# OSSC_HDMI_Audio_v1_5_A4a.net
KiCad netlist of a schematic drawn in EAGLE
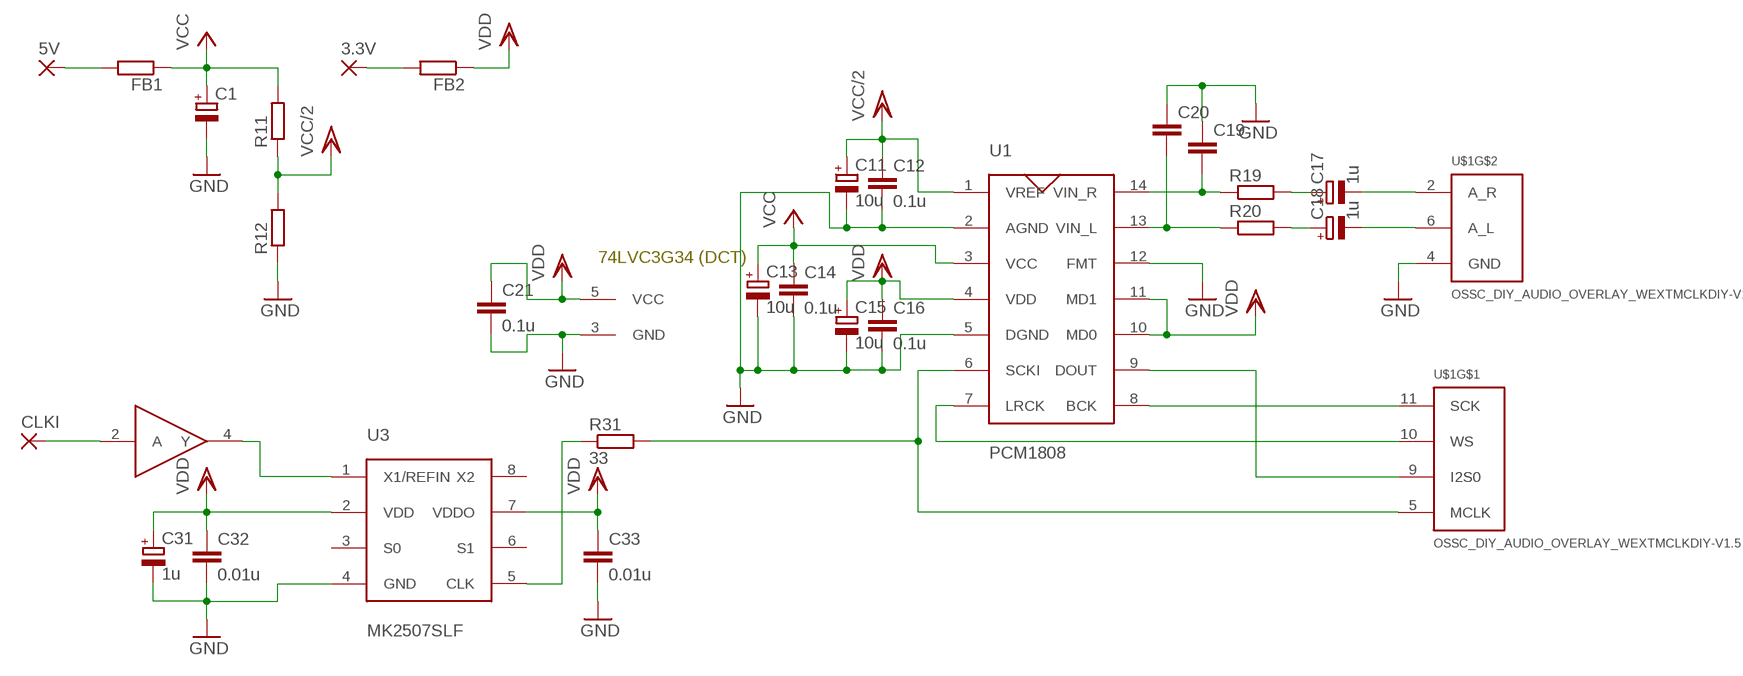
[diagram p0: schematic, sheet 1]

(export (version "E")
  (design (tool "Eeschema 10.0.6"))
  (components
    (comp (ref "3.3V")
      (value "SMD2")
      (footprint "eagle-import:SMD1,27-2,54")
      (libsource (lib "eagle-import") (part "SMD2"))
    )
    (comp (ref "5V")
      (value "SMD2")
      (footprint "eagle-import:SMD1,27-2,54")
      (libsource (lib "eagle-import") (part "SMD2"))
    )
    (comp (ref "C1")
      (value "CPOL-EUSMCC")
      (footprint "eagle-import:SMC_C")
      (libsource (lib "eagle-import") (part "CPOL-EUSMCC"))
    )
    (comp (ref "C11")
      (value "10u")
      (footprint "eagle-import:SMC_A")
      (libsource (lib "eagle-import") (part "CPOL-EUSMCA"))
    )
    (comp (ref "C12")
      (value "0.1u")
      (footprint "eagle-import:C0603")
      (libsource (lib "eagle-import") (part "C-EUC0603"))
    )
    (comp (ref "C13")
      (value "10u")
      (footprint "eagle-import:SMC_A")
      (libsource (lib "eagle-import") (part "CPOL-EUSMCA"))
    )
    (comp (ref "C14")
      (value "0.1u")
      (footprint "eagle-import:C0603")
      (libsource (lib "eagle-import") (part "C-EUC0603"))
    )
    (comp (ref "C15")
      (value "10u")
      (footprint "eagle-import:SMC_A")
      (libsource (lib "eagle-import") (part "CPOL-EUSMCA"))
    )
    (comp (ref "C16")
      (value "0.1u")
      (footprint "eagle-import:C0603")
      (libsource (lib "eagle-import") (part "C-EUC0603"))
    )
    (comp (ref "C17")
      (value "1u")
      (footprint "eagle-import:SMC_A")
      (libsource (lib "eagle-import") (part "CPOL-EUSMCA"))
    )
    (comp (ref "C18")
      (value "1u")
      (footprint "eagle-import:SMC_A")
      (libsource (lib "eagle-import") (part "CPOL-EUSMCA"))
    )
    (comp (ref "C19")
      (value "C-EUC0603")
      (footprint "eagle-import:C0603")
      (libsource (lib "eagle-import") (part "C-EUC0603"))
    )
    (comp (ref "C20")
      (value "C-EUC0603")
      (footprint "eagle-import:C0603")
      (libsource (lib "eagle-import") (part "C-EUC0603"))
    )
    (comp (ref "C21")
      (value "0.1u")
      (footprint "eagle-import:C0603")
      (libsource (lib "eagle-import") (part "C-EUC0603"))
    )
    (comp (ref "C31")
      (value "1u")
      (footprint "eagle-import:SMC_A")
      (libsource (lib "eagle-import") (part "CPOL-EUSMCA"))
    )
    (comp (ref "C32")
      (value "0.01u")
      (footprint "eagle-import:C0603")
      (libsource (lib "eagle-import") (part "C-EUC0603"))
    )
    (comp (ref "C33")
      (value "0.01u")
      (footprint "eagle-import:C0603")
      (libsource (lib "eagle-import") (part "C-EUC0603"))
    )
    (comp (ref "CLKI")
      (value "SMD2")
      (footprint "eagle-import:SMD1,27-2,54")
      (libsource (lib "eagle-import") (part "SMD2"))
    )
    (comp (ref "FB1")
      (value "R-EU_R0603")
      (footprint "eagle-import:R0603")
      (libsource (lib "eagle-import") (part "R-EU_R0603"))
    )
    (comp (ref "FB2")
      (value "R-EU_R0603")
      (footprint "eagle-import:R0603")
      (libsource (lib "eagle-import") (part "R-EU_R0603"))
    )
    (comp (ref "R11")
      (value "R-EU_R0603")
      (footprint "eagle-import:R0603")
      (libsource (lib "eagle-import") (part "R-EU_R0603"))
    )
    (comp (ref "R12")
      (value "R-EU_R0603")
      (footprint "eagle-import:R0603")
      (libsource (lib "eagle-import") (part "R-EU_R0603"))
    )
    (comp (ref "R19")
      (value "R-EU_R0603")
      (footprint "eagle-import:R0603")
      (libsource (lib "eagle-import") (part "R-EU_R0603"))
    )
    (comp (ref "R20")
      (value "R-EU_R0603")
      (footprint "eagle-import:R0603")
      (libsource (lib "eagle-import") (part "R-EU_R0603"))
    )
    (comp (ref "R31")
      (value "33")
      (footprint "eagle-import:R0603")
      (libsource (lib "eagle-import") (part "R-EU_R0603"))
    )
    (comp (ref "U$1")
      (value "OSSC_DIY_AUDIO_OVERLAY_WEXTMCLKDIY-V1.5")
      (footprint "eagle-import:OSSC_OVERLAY_V1.5_WEXTMCLK")
      (libsource (lib "eagle-import") (part "OSSC_DIY_AUDIO_OVERLAY_WEXTMCLKDIY-V1.5"))
    )
    (comp (ref "U1")
      (value "PCM1808")
      (footprint "eagle-import:PCM1808")
      (libsource (lib "eagle-import") (part "PCM1808"))
    )
    (comp (ref "U2")
      (value "74LVC1G34")
      (footprint "eagle-import:74LVC1G34DCK")
      (libsource (lib "eagle-import") (part "74LVC1G34"))
    )
    (comp (ref "U3")
      (value "MK2507SLF")
      (footprint "eagle-import:SOIC8")
      (libsource (lib "eagle-import") (part "MK2507SLF"))
    )
  )
  (nets
    (net (code "1") (name "GND") (class "Default")
      (node (ref "C1") (pin "-") (pinfunction "-_-") (pintype "passive"))
      (node (ref "C11") (pin "-") (pinfunction "-_-") (pintype "passive"))
      (node (ref "C12") (pin "2") (pinfunction "2_2") (pintype "passive"))
      (node (ref "C13") (pin "-") (pinfunction "-_-") (pintype "passive"))
      (node (ref "C14") (pin "2") (pinfunction "2_2") (pintype "passive"))
      (node (ref "C15") (pin "-") (pinfunction "-_-") (pintype "passive"))
      (node (ref "C16") (pin "2") (pinfunction "2_2") (pintype "passive"))
      (node (ref "C19") (pin "1") (pinfunction "1_1") (pintype "passive"))
      (node (ref "C20") (pin "1") (pinfunction "1_1") (pintype "passive"))
      (node (ref "C21") (pin "2") (pinfunction "2_2") (pintype "passive"))
      (node (ref "C31") (pin "-") (pinfunction "-_-") (pintype "passive"))
      (node (ref "C32") (pin "2") (pinfunction "2_2") (pintype "passive"))
      (node (ref "C33") (pin "2") (pinfunction "2_2") (pintype "passive"))
      (node (ref "R12") (pin "1") (pinfunction "1_1") (pintype "passive"))
      (node (ref "U$1") (pin "4") (pinfunction "GND_4") (pintype "bidirectional"))
      (node (ref "U1") (pin "12") (pinfunction "FMT_12") (pintype "bidirectional"))
      (node (ref "U1") (pin "2") (pinfunction "AGND_2") (pintype "bidirectional"))
      (node (ref "U1") (pin "5") (pinfunction "DGND_5") (pintype "bidirectional"))
      (node (ref "U2") (pin "3") (pinfunction "GND_3") (pintype "bidirectional"))
      (node (ref "U3") (pin "4") (pinfunction "GND_4") (pintype "bidirectional"))
    )
    (net (code "2") (name "Net-(3.3V-P)") (class "Default")
      (node (ref "3.3V") (pin "1") (pinfunction "P_1") (pintype "passive"))
      (node (ref "FB2") (pin "2") (pinfunction "2_2") (pintype "passive"))
    )
    (net (code "3") (name "Net-(5V-P)") (class "Default")
      (node (ref "5V") (pin "1") (pinfunction "P_1") (pintype "passive"))
      (node (ref "FB1") (pin "2") (pinfunction "2_2") (pintype "passive"))
    )
    (net (code "4") (name "Net-(C17-Pad+)") (class "Default")
      (node (ref "C17") (pin "+") (pinfunction "+_+") (pintype "passive"))
      (node (ref "R19") (pin "2") (pinfunction "2_2") (pintype "passive"))
    )
    (net (code "5") (name "Net-(C18-Pad+)") (class "Default")
      (node (ref "C18") (pin "+") (pinfunction "+_+") (pintype "passive"))
      (node (ref "R20") (pin "2") (pinfunction "2_2") (pintype "passive"))
    )
    (net (code "6") (name "Net-(CLKI-P)") (class "Default")
      (node (ref "CLKI") (pin "1") (pinfunction "P_1") (pintype "passive"))
      (node (ref "U2") (pin "2") (pinfunction "A_2") (pintype "bidirectional"))
    )
    (net (code "7") (name "Net-(U$1A-I2S0)") (class "Default")
      (node (ref "U$1") (pin "9") (pinfunction "I2S0_9") (pintype "bidirectional"))
      (node (ref "U1") (pin "9") (pinfunction "DOUT_9") (pintype "bidirectional"))
    )
    (net (code "8") (name "Net-(U$1A-MCLK)") (class "Default")
      (node (ref "R31") (pin "2") (pinfunction "2_2") (pintype "passive"))
      (node (ref "U$1") (pin "5") (pinfunction "MCLK_5") (pintype "bidirectional"))
      (node (ref "U1") (pin "6") (pinfunction "SCKI_6") (pintype "bidirectional"))
    )
    (net (code "9") (name "Net-(U$1A-SCK)") (class "Default")
      (node (ref "U$1") (pin "11") (pinfunction "SCK_11") (pintype "bidirectional"))
      (node (ref "U1") (pin "8") (pinfunction "BCK_8") (pintype "bidirectional"))
    )
    (net (code "10") (name "Net-(U$1A-WS)") (class "Default")
      (node (ref "U$1") (pin "10") (pinfunction "WS_10") (pintype "bidirectional"))
      (node (ref "U1") (pin "7") (pinfunction "LRCK_7") (pintype "bidirectional"))
    )
    (net (code "11") (name "Net-(U$1B-A_L)") (class "Default")
      (node (ref "C18") (pin "-") (pinfunction "-_-") (pintype "passive"))
      (node (ref "U$1") (pin "6") (pinfunction "A_L_6") (pintype "bidirectional"))
    )
    (net (code "12") (name "Net-(U$1B-A_R)") (class "Default")
      (node (ref "C17") (pin "-") (pinfunction "-_-") (pintype "passive"))
      (node (ref "U$1") (pin "2") (pinfunction "A_R_2") (pintype "bidirectional"))
    )
    (net (code "13") (name "Net-(U1-VIN_L)") (class "Default")
      (node (ref "C20") (pin "2") (pinfunction "2_2") (pintype "passive"))
      (node (ref "R20") (pin "1") (pinfunction "1_1") (pintype "passive"))
      (node (ref "U1") (pin "13") (pinfunction "VIN_L_13") (pintype "bidirectional"))
    )
    (net (code "14") (name "Net-(U1-VIN_R)") (class "Default")
      (node (ref "C19") (pin "2") (pinfunction "2_2") (pintype "passive"))
      (node (ref "R19") (pin "1") (pinfunction "1_1") (pintype "passive"))
      (node (ref "U1") (pin "14") (pinfunction "VIN_R_14") (pintype "bidirectional"))
    )
    (net (code "15") (name "Net-(U2A-Y)") (class "Default")
      (node (ref "U2") (pin "4") (pinfunction "Y_4") (pintype "bidirectional"))
      (node (ref "U3") (pin "1") (pinfunction "X1/REFIN_1") (pintype "bidirectional"))
    )
    (net (code "16") (name "Net-(U3-CLK)") (class "Default")
      (node (ref "R31") (pin "1") (pinfunction "1_1") (pintype "passive"))
      (node (ref "U3") (pin "5") (pinfunction "CLK_5") (pintype "bidirectional"))
    )
    (net (code "17") (name "VCC") (class "Default")
      (node (ref "C1") (pin "+") (pinfunction "+_+") (pintype "passive"))
      (node (ref "C13") (pin "+") (pinfunction "+_+") (pintype "passive"))
      (node (ref "C14") (pin "1") (pinfunction "1_1") (pintype "passive"))
      (node (ref "FB1") (pin "1") (pinfunction "1_1") (pintype "passive"))
      (node (ref "R11") (pin "2") (pinfunction "2_2") (pintype "passive"))
      (node (ref "U1") (pin "3") (pinfunction "VCC_3") (pintype "bidirectional"))
    )
    (net (code "18") (name "VCC{slash}2") (class "Default")
      (node (ref "C11") (pin "+") (pinfunction "+_+") (pintype "passive"))
      (node (ref "C12") (pin "1") (pinfunction "1_1") (pintype "passive"))
      (node (ref "R11") (pin "1") (pinfunction "1_1") (pintype "passive"))
      (node (ref "R12") (pin "2") (pinfunction "2_2") (pintype "passive"))
      (node (ref "U1") (pin "1") (pinfunction "VREF_1") (pintype "bidirectional"))
    )
    (net (code "19") (name "VDD") (class "Default")
      (node (ref "C15") (pin "+") (pinfunction "+_+") (pintype "passive"))
      (node (ref "C16") (pin "1") (pinfunction "1_1") (pintype "passive"))
      (node (ref "C21") (pin "1") (pinfunction "1_1") (pintype "passive"))
      (node (ref "C31") (pin "+") (pinfunction "+_+") (pintype "passive"))
      (node (ref "C32") (pin "1") (pinfunction "1_1") (pintype "passive"))
      (node (ref "C33") (pin "1") (pinfunction "1_1") (pintype "passive"))
      (node (ref "FB2") (pin "1") (pinfunction "1_1") (pintype "passive"))
      (node (ref "U1") (pin "10") (pinfunction "MD0_10") (pintype "bidirectional"))
      (node (ref "U1") (pin "11") (pinfunction "MD1_11") (pintype "bidirectional"))
      (node (ref "U1") (pin "4") (pinfunction "VDD_4") (pintype "bidirectional"))
      (node (ref "U2") (pin "5") (pinfunction "VCC_5") (pintype "bidirectional"))
      (node (ref "U3") (pin "2") (pinfunction "VDD_2") (pintype "bidirectional"))
      (node (ref "U3") (pin "7") (pinfunction "VDDO_7") (pintype "bidirectional"))
    )
    (net (code "20") (name "unconnected-(U3-S0-Pad3)") (class "Default")
      (node (ref "U3") (pin "3") (pinfunction "S0_3") (pintype "bidirectional"))
    )
    (net (code "21") (name "unconnected-(U3-S1-Pad6)") (class "Default")
      (node (ref "U3") (pin "6") (pinfunction "S1_6") (pintype "bidirectional"))
    )
    (net (code "22") (name "unconnected-(U3-X2-Pad8)") (class "Default")
      (node (ref "U3") (pin "8") (pinfunction "X2_8") (pintype "bidirectional"))
    )
  )
)
